# MCU.net
KiCad netlist of a schematic drawn in Altium Designer
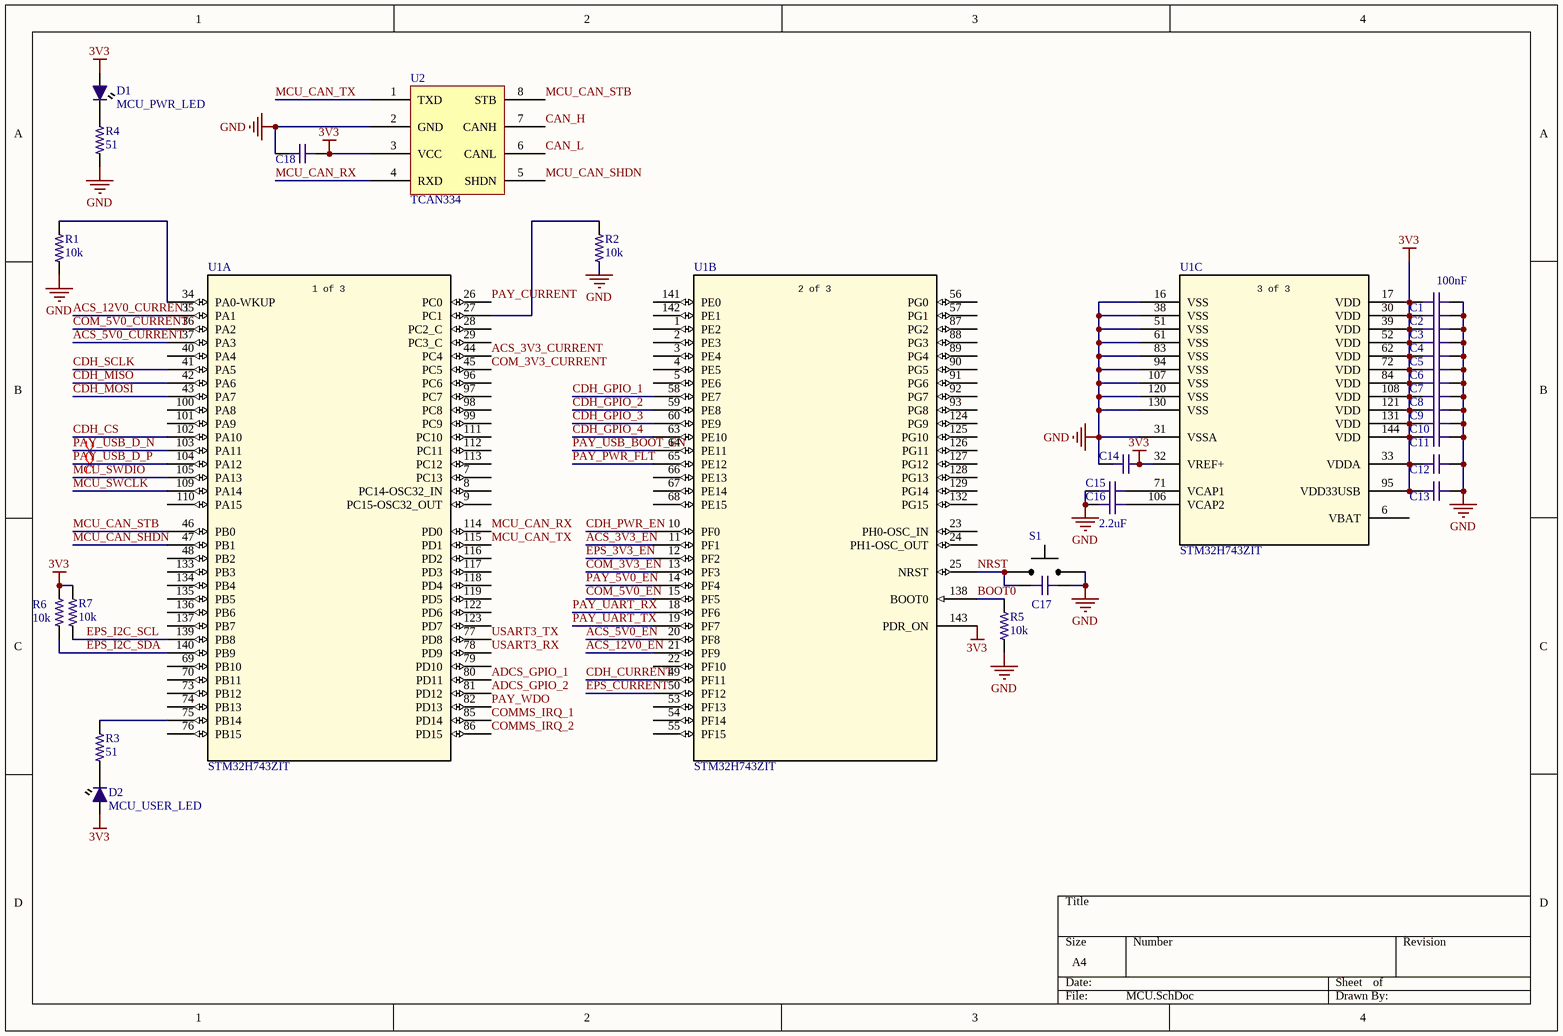
[diagram p0: MCU.SchDoc]

(export (version "E")
  (design (tool "Eeschema 10.0.6"))
  (components
    (comp (ref "C1")
      (value "100nF")
      (footprint "C0603-IPC")
      (description "Chip Capacitor, 0603, 100nF, 10V, X7R")
      (fields (field (name "Comment") "Capacitor"))
      (libsource (lib "UBC_Orbit_Shared_Components") (part "Capacitor"))
    )
    (comp (ref "C2")
      (value "Capacitor")
      (footprint "C0603-IPC")
      (description "Chip Capacitor, 0603, 100nF, 10V, X7R")
      (libsource (lib "UBC_Orbit_Shared_Components") (part "Capacitor"))
    )
    (comp (ref "C3")
      (value "Capacitor")
      (footprint "C0603-IPC")
      (description "Chip Capacitor, 0603, 100nF, 10V, X7R")
      (libsource (lib "UBC_Orbit_Shared_Components") (part "Capacitor"))
    )
    (comp (ref "C4")
      (value "Capacitor")
      (footprint "C0603-IPC")
      (description "Chip Capacitor, 0603, 100nF, 10V, X7R")
      (libsource (lib "UBC_Orbit_Shared_Components") (part "Capacitor"))
    )
    (comp (ref "C5")
      (value "Capacitor")
      (footprint "C0603-IPC")
      (description "Chip Capacitor, 0603, 100nF, 10V, X7R")
      (libsource (lib "UBC_Orbit_Shared_Components") (part "Capacitor"))
    )
    (comp (ref "C6")
      (value "Capacitor")
      (footprint "C0603-IPC")
      (description "Chip Capacitor, 0603, 100nF, 10V, X7R")
      (libsource (lib "UBC_Orbit_Shared_Components") (part "Capacitor"))
    )
    (comp (ref "C7")
      (value "Capacitor")
      (footprint "C0603-IPC")
      (description "Chip Capacitor, 0603, 100nF, 10V, X7R")
      (libsource (lib "UBC_Orbit_Shared_Components") (part "Capacitor"))
    )
    (comp (ref "C8")
      (value "Capacitor")
      (footprint "C0603-IPC")
      (description "Chip Capacitor, 0603, 100nF, 10V, X7R")
      (libsource (lib "UBC_Orbit_Shared_Components") (part "Capacitor"))
    )
    (comp (ref "C9")
      (value "Capacitor")
      (footprint "C0603-IPC")
      (description "Chip Capacitor, 0603, 100nF, 10V, X7R")
      (libsource (lib "UBC_Orbit_Shared_Components") (part "Capacitor"))
    )
    (comp (ref "C10")
      (value "Capacitor")
      (footprint "C0603-IPC")
      (description "Chip Capacitor, 0603, 100nF, 10V, X7R")
      (libsource (lib "UBC_Orbit_Shared_Components") (part "Capacitor"))
    )
    (comp (ref "C11")
      (value "Capacitor")
      (footprint "C0603-IPC")
      (description "Chip Capacitor, 0603, 100nF, 10V, X7R")
      (libsource (lib "UBC_Orbit_Shared_Components") (part "Capacitor"))
    )
    (comp (ref "C12")
      (value "Capacitor")
      (footprint "C0603-IPC")
      (description "Chip Capacitor, 0603, 100nF, 10V, X7R")
      (libsource (lib "UBC_Orbit_Shared_Components") (part "Capacitor"))
    )
    (comp (ref "C13")
      (value "Capacitor")
      (footprint "C0603-IPC")
      (description "Chip Capacitor, 0603, 100nF, 10V, X7R")
      (libsource (lib "UBC_Orbit_Shared_Components") (part "Capacitor"))
    )
    (comp (ref "C14")
      (value "Capacitor")
      (footprint "C0603-IPC")
      (description "Chip Capacitor, 0603, 10nF, 10V, X7R")
      (libsource (lib "UBC_Orbit_Shared_Components") (part "Capacitor"))
    )
    (comp (ref "C15")
      (value "Capacitor")
      (footprint "C0603-IPC")
      (description "Chip Capacitor, 0603, 2.2uF, 10V, X7R")
      (libsource (lib "UBC_Orbit_Shared_Components") (part "Capacitor"))
    )
    (comp (ref "C16")
      (value "2.2uF")
      (footprint "C0603-IPC")
      (description "Chip Capacitor, 0603, 2.2uF, 10V, X7R")
      (fields (field (name "Comment") "Capacitor"))
      (libsource (lib "UBC_Orbit_Shared_Components") (part "Capacitor"))
    )
    (comp (ref "C17")
      (value "Capacitor")
      (footprint "C0603-IPC")
      (description "Chip Capacitor, 0603, 100nF, 10V, X7R")
      (libsource (lib "UBC_Orbit_Shared_Components") (part "Capacitor"))
    )
    (comp (ref "C18")
      (value "Capacitor")
      (footprint "C0603-IPC")
      (description "Chip Capacitor, 0603, 100nF, 10V, X7R")
      (libsource (lib "UBC_Orbit_Shared_Components") (part "Capacitor"))
    )
    (comp (ref "D1")
      (value "MCU_PWR_LED")
      (footprint "LED0603-IPC")
      (description "Red PWR_LED")
      (libsource (lib "Diodes") (part "LED 0603 SMD"))
    )
    (comp (ref "D2")
      (value "MCU_USER_LED")
      (footprint "LED0603-IPC")
      (description "Blue DEBUG_LED")
      (libsource (lib "Diodes") (part "LED 0603 SMD"))
    )
    (comp (ref "R1")
      (value "10k")
      (footprint "R0603-IPC")
      (description "Resistor (0603)")
      (fields (field (name "Comment") "Resistor"))
      (libsource (lib "UBC_Orbit_Shared_Components") (part "Resistor"))
    )
    (comp (ref "R2")
      (value "10k")
      (footprint "R0603-IPC")
      (description "Resistor (0603)")
      (fields (field (name "Comment") "Resistor"))
      (libsource (lib "UBC_Orbit_Shared_Components") (part "Resistor"))
    )
    (comp (ref "R3")
      (value "51")
      (footprint "R0603-IPC")
      (description "Resistor (0603)")
      (fields (field (name "Comment") "Resistor"))
      (libsource (lib "UBC_Orbit_Shared_Components") (part "Resistor"))
    )
    (comp (ref "R4")
      (value "51")
      (footprint "R0603-IPC")
      (description "Chip Resistor, 0603, 51hms, 0.1W")
      (fields (field (name "Comment") "0603 Template"))
      (libsource (lib "Resistors") (part "0603 Template"))
    )
    (comp (ref "R5")
      (value "10k")
      (footprint "R0603-IPC")
      (description "Resistor (0603)")
      (fields (field (name "Comment") "Resistor"))
      (libsource (lib "UBC_Orbit_Shared_Components") (part "Resistor"))
    )
    (comp (ref "R6")
      (value "10k")
      (footprint "R0603-IPC")
      (description "Resistor (0603)")
      (fields (field (name "Comment") "Resistor"))
      (libsource (lib "UBC_Orbit_Shared_Components") (part "Resistor"))
    )
    (comp (ref "R7")
      (value "10k")
      (footprint "R0603-IPC")
      (description "Resistor (0603)")
      (fields (field (name "Comment") "Resistor"))
      (libsource (lib "UBC_Orbit_Shared_Components") (part "Resistor"))
    )
    (comp (ref "S1")
      (value "PTS810")
      (footprint "PTS810")
      (description "PTS810 Switch (Tactile)")
      (fields (field (name "MANUFACTURER") "C&K") (field (name "PART NUMBER") "PTS810 SJM 250 SMTR LFS"))
      (libsource (lib "UBC_Orbit_Shared_Components") (part "PTS810"))
    )
    (comp (ref "U1")
      (value "STM32H743ZIT")
      (footprint "LQFP50P2200X2200X160-144N")
      (description "STM32H743ZIT MCU")
      (fields (field (name "MANUFACTURER") "STMicroelectronics") (field (name "PART NUMBER") "STM32H743ZIT6"))
      (libsource (lib "UBC_Orbit_Shared_Components") (part "STM32H743ZIT"))
    )
    (comp (ref "U2")
      (value "TCAN334")
      (footprint "SOIC127P600X175-8N")
      (description "TCAN334 CAN Transceiver")
      (fields (field (name "MANUFACTURER") "Texas Instruments") (field (name "PART NUMBER") "TCAN334DCNT"))
      (libsource (lib "UBC_Orbit_Shared_Components") (part "TCAN334"))
    )
  )
  (nets
    (net (code "1") (name "/ACS_3V3_CURRENT") (class "Default")
      (node (ref "U1") (pin "44") (pinfunction "PC4_44") (pintype "bidirectional"))
    )
    (net (code "2") (name "/ACS_3V3_EN") (class "Default")
      (node (ref "U1") (pin "11") (pinfunction "PF1_11") (pintype "bidirectional"))
    )
    (net (code "3") (name "/ACS_5V0_CURRENT") (class "Default")
      (node (ref "U1") (pin "37") (pinfunction "PA3_37") (pintype "bidirectional"))
    )
    (net (code "4") (name "/ACS_5V0_EN") (class "Default")
      (node (ref "U1") (pin "20") (pinfunction "PF8_20") (pintype "bidirectional"))
    )
    (net (code "5") (name "/ACS_12V0_CURRENT") (class "Default")
      (node (ref "U1") (pin "35") (pinfunction "PA1_35") (pintype "bidirectional"))
    )
    (net (code "6") (name "/ACS_12V0_EN") (class "Default")
      (node (ref "U1") (pin "21") (pinfunction "PF9_21") (pintype "bidirectional"))
    )
    (net (code "7") (name "/ADCS_GPIO_1") (class "Default")
      (node (ref "U1") (pin "80") (pinfunction "PD11_80") (pintype "bidirectional"))
    )
    (net (code "8") (name "/ADCS_GPIO_2") (class "Default")
      (node (ref "U1") (pin "81") (pinfunction "PD12_81") (pintype "bidirectional"))
    )
    (net (code "9") (name "/BOOT0") (class "Default")
      (node (ref "R5") (pin "2") (pintype "passive"))
      (node (ref "U1") (pin "138") (pinfunction "BOOT0_138") (pintype "input"))
    )
    (net (code "10") (name "/CAN_H") (class "Default")
      (node (ref "U2") (pin "7") (pinfunction "CANH_7") (pintype "passive"))
    )
    (net (code "11") (name "/CAN_L") (class "Default")
      (node (ref "U2") (pin "6") (pinfunction "CANL_6") (pintype "passive"))
    )
    (net (code "12") (name "/CDH_CS") (class "Default")
      (node (ref "U1") (pin "102") (pinfunction "PA10_102") (pintype "bidirectional"))
    )
    (net (code "13") (name "/CDH_CURRENT") (class "Default")
      (node (ref "U1") (pin "49") (pinfunction "PF11_49") (pintype "bidirectional"))
    )
    (net (code "14") (name "/CDH_GPIO_1") (class "Default")
      (node (ref "U1") (pin "58") (pinfunction "PE7_58") (pintype "bidirectional"))
    )
    (net (code "15") (name "/CDH_GPIO_2") (class "Default")
      (node (ref "U1") (pin "59") (pinfunction "PE8_59") (pintype "bidirectional"))
    )
    (net (code "16") (name "/CDH_GPIO_3") (class "Default")
      (node (ref "U1") (pin "60") (pinfunction "PE9_60") (pintype "bidirectional"))
    )
    (net (code "17") (name "/CDH_GPIO_4") (class "Default")
      (node (ref "U1") (pin "63") (pinfunction "PE10_63") (pintype "bidirectional"))
    )
    (net (code "18") (name "/CDH_MISO") (class "Default")
      (node (ref "U1") (pin "42") (pinfunction "PA6_42") (pintype "bidirectional"))
    )
    (net (code "19") (name "/CDH_MOSI") (class "Default")
      (node (ref "U1") (pin "43") (pinfunction "PA7_43") (pintype "bidirectional"))
    )
    (net (code "20") (name "/CDH_PWR_EN") (class "Default")
      (node (ref "U1") (pin "10") (pinfunction "PF0_10") (pintype "bidirectional"))
    )
    (net (code "21") (name "/CDH_SCLK") (class "Default")
      (node (ref "U1") (pin "41") (pinfunction "PA5_41") (pintype "bidirectional"))
    )
    (net (code "22") (name "/COMMS_IRQ_1") (class "Default")
      (node (ref "U1") (pin "85") (pinfunction "PD14_85") (pintype "bidirectional"))
    )
    (net (code "23") (name "/COMMS_IRQ_2") (class "Default")
      (node (ref "U1") (pin "86") (pinfunction "PD15_86") (pintype "bidirectional"))
    )
    (net (code "24") (name "/COM_3V3_CURRENT") (class "Default")
      (node (ref "U1") (pin "45") (pinfunction "PC5_45") (pintype "bidirectional"))
    )
    (net (code "25") (name "/COM_3V3_EN") (class "Default")
      (node (ref "U1") (pin "13") (pinfunction "PF3_13") (pintype "bidirectional"))
    )
    (net (code "26") (name "/COM_5V0_CURRENT") (class "Default")
      (node (ref "U1") (pin "36") (pinfunction "PA2_36") (pintype "bidirectional"))
    )
    (net (code "27") (name "/COM_5V0_EN") (class "Default")
      (node (ref "U1") (pin "15") (pinfunction "PF5_15") (pintype "bidirectional"))
    )
    (net (code "28") (name "/EPS_3V3_EN") (class "Default")
      (node (ref "U1") (pin "12") (pinfunction "PF2_12") (pintype "bidirectional"))
    )
    (net (code "29") (name "/EPS_CURRENT") (class "Default")
      (node (ref "U1") (pin "50") (pinfunction "PF12_50") (pintype "bidirectional"))
    )
    (net (code "30") (name "/EPS_I2C_SCL") (class "Default")
      (node (ref "R7") (pin "1") (pintype "passive"))
      (node (ref "U1") (pin "139") (pinfunction "PB8_139") (pintype "bidirectional"))
    )
    (net (code "31") (name "/EPS_I2C_SDA") (class "Default")
      (node (ref "R6") (pin "1") (pintype "passive"))
      (node (ref "U1") (pin "140") (pinfunction "PB9_140") (pintype "bidirectional"))
    )
    (net (code "32") (name "/MCU_CAN_RX") (class "Default")
      (node (ref "U1") (pin "114") (pinfunction "PD0_114") (pintype "bidirectional"))
      (node (ref "U2") (pin "4") (pinfunction "RXD_4") (pintype "passive"))
    )
    (net (code "33") (name "/MCU_CAN_SHDN") (class "Default")
      (node (ref "U1") (pin "47") (pinfunction "PB1_47") (pintype "bidirectional"))
      (node (ref "U2") (pin "5") (pinfunction "SHDN_5") (pintype "passive"))
    )
    (net (code "34") (name "/MCU_CAN_STB") (class "Default")
      (node (ref "U1") (pin "46") (pinfunction "PB0_46") (pintype "bidirectional"))
      (node (ref "U2") (pin "8") (pinfunction "STB_8") (pintype "passive"))
    )
    (net (code "35") (name "/MCU_CAN_TX") (class "Default")
      (node (ref "U1") (pin "115") (pinfunction "PD1_115") (pintype "bidirectional"))
      (node (ref "U2") (pin "1") (pinfunction "TXD_1") (pintype "passive"))
    )
    (net (code "36") (name "/MCU_SWCLK") (class "Default")
      (node (ref "U1") (pin "109") (pinfunction "PA14_109") (pintype "bidirectional"))
    )
    (net (code "37") (name "/MCU_SWDIO") (class "Default")
      (node (ref "U1") (pin "105") (pinfunction "PA13_105") (pintype "bidirectional"))
    )
    (net (code "38") (name "/NRST") (class "Default")
      (node (ref "C17") (pin "1") (pintype "passive"))
      (node (ref "S1") (pin "1") (pinfunction "1_1") (pintype "passive"))
      (node (ref "U1") (pin "25") (pinfunction "NRST_25") (pintype "bidirectional"))
    )
    (net (code "39") (name "/PAY_5V0_EN") (class "Default")
      (node (ref "U1") (pin "14") (pinfunction "PF4_14") (pintype "bidirectional"))
    )
    (net (code "40") (name "/PAY_CURRENT") (class "Default")
      (node (ref "U1") (pin "26") (pinfunction "PC0_26") (pintype "bidirectional"))
    )
    (net (code "41") (name "/PAY_PWR_FLT") (class "Default")
      (node (ref "U1") (pin "65") (pinfunction "PE12_65") (pintype "bidirectional"))
    )
    (net (code "42") (name "/PAY_UART_RX") (class "Default")
      (node (ref "U1") (pin "18") (pinfunction "PF6_18") (pintype "bidirectional"))
    )
    (net (code "43") (name "/PAY_UART_TX") (class "Default")
      (node (ref "U1") (pin "19") (pinfunction "PF7_19") (pintype "bidirectional"))
    )
    (net (code "44") (name "/PAY_USB_BOOT_EN") (class "Default")
      (node (ref "U1") (pin "64") (pinfunction "PE11_64") (pintype "bidirectional"))
    )
    (net (code "45") (name "/PAY_USB_D_N") (class "Default")
      (node (ref "U1") (pin "103") (pinfunction "PA11_103") (pintype "bidirectional"))
    )
    (net (code "46") (name "/PAY_USB_D_P") (class "Default")
      (node (ref "U1") (pin "104") (pinfunction "PA12_104") (pintype "bidirectional"))
    )
    (net (code "47") (name "/PAY_WDO") (class "Default")
      (node (ref "U1") (pin "82") (pinfunction "PD13_82") (pintype "bidirectional"))
    )
    (net (code "48") (name "/USART3_RX") (class "Default")
      (node (ref "U1") (pin "78") (pinfunction "PD9_78") (pintype "bidirectional"))
    )
    (net (code "49") (name "/USART3_TX") (class "Default")
      (node (ref "U1") (pin "77") (pinfunction "PD8_77") (pintype "bidirectional"))
    )
    (net (code "50") (name "3V3") (class "Default")
      (node (ref "C1") (pin "1") (pintype "passive"))
      (node (ref "C10") (pin "1") (pintype "passive"))
      (node (ref "C11") (pin "1") (pintype "passive"))
      (node (ref "C12") (pin "1") (pintype "passive"))
      (node (ref "C13") (pin "1") (pintype "passive"))
      (node (ref "C14") (pin "2") (pintype "passive"))
      (node (ref "C18") (pin "2") (pintype "passive"))
      (node (ref "C2") (pin "1") (pintype "passive"))
      (node (ref "C3") (pin "1") (pintype "passive"))
      (node (ref "C4") (pin "1") (pintype "passive"))
      (node (ref "C5") (pin "1") (pintype "passive"))
      (node (ref "C6") (pin "1") (pintype "passive"))
      (node (ref "C7") (pin "1") (pintype "passive"))
      (node (ref "C8") (pin "1") (pintype "passive"))
      (node (ref "C9") (pin "1") (pintype "passive"))
      (node (ref "D1") (pin "A") (pintype "passive"))
      (node (ref "D2") (pin "A") (pintype "passive"))
      (node (ref "R6") (pin "2") (pintype "passive"))
      (node (ref "R7") (pin "2") (pintype "passive"))
      (node (ref "U1") (pin "108") (pinfunction "VDD_108") (pintype "power_in"))
      (node (ref "U1") (pin "121") (pinfunction "VDD_121") (pintype "power_in"))
      (node (ref "U1") (pin "131") (pinfunction "VDD_131") (pintype "power_in"))
      (node (ref "U1") (pin "143") (pinfunction "PDR_ON_143") (pintype "passive"))
      (node (ref "U1") (pin "144") (pinfunction "VDD_144") (pintype "power_in"))
      (node (ref "U1") (pin "17") (pinfunction "VDD_17") (pintype "power_in"))
      (node (ref "U1") (pin "30") (pinfunction "VDD_30") (pintype "power_in"))
      (node (ref "U1") (pin "32") (pinfunction "VREF+_32") (pintype "power_in"))
      (node (ref "U1") (pin "33") (pinfunction "VDDA_33") (pintype "power_in"))
      (node (ref "U1") (pin "39") (pinfunction "VDD_39") (pintype "power_in"))
      (node (ref "U1") (pin "52") (pinfunction "VDD_52") (pintype "power_in"))
      (node (ref "U1") (pin "62") (pinfunction "VDD_62") (pintype "power_in"))
      (node (ref "U1") (pin "72") (pinfunction "VDD_72") (pintype "power_in"))
      (node (ref "U1") (pin "84") (pinfunction "VDD_84") (pintype "power_in"))
      (node (ref "U1") (pin "95") (pinfunction "VDD33USB_95") (pintype "power_in"))
      (node (ref "U2") (pin "3") (pinfunction "VCC_3") (pintype "passive"))
    )
    (net (code "51") (name "GND") (class "Default")
      (node (ref "C1") (pin "2") (pintype "passive"))
      (node (ref "C10") (pin "2") (pintype "passive"))
      (node (ref "C11") (pin "2") (pintype "passive"))
      (node (ref "C12") (pin "2") (pintype "passive"))
      (node (ref "C13") (pin "2") (pintype "passive"))
      (node (ref "C14") (pin "1") (pintype "passive"))
      (node (ref "C15") (pin "1") (pintype "passive"))
      (node (ref "C16") (pin "1") (pintype "passive"))
      (node (ref "C17") (pin "2") (pintype "passive"))
      (node (ref "C18") (pin "1") (pintype "passive"))
      (node (ref "C2") (pin "2") (pintype "passive"))
      (node (ref "C3") (pin "2") (pintype "passive"))
      (node (ref "C4") (pin "2") (pintype "passive"))
      (node (ref "C5") (pin "2") (pintype "passive"))
      (node (ref "C6") (pin "2") (pintype "passive"))
      (node (ref "C7") (pin "2") (pintype "passive"))
      (node (ref "C8") (pin "2") (pintype "passive"))
      (node (ref "C9") (pin "2") (pintype "passive"))
      (node (ref "R1") (pin "1") (pintype "passive"))
      (node (ref "R2") (pin "1") (pintype "passive"))
      (node (ref "R4") (pin "2") (pintype "passive"))
      (node (ref "R5") (pin "1") (pintype "passive"))
      (node (ref "S1") (pin "2") (pinfunction "2_2") (pintype "passive"))
      (node (ref "U1") (pin "107") (pinfunction "VSS_107") (pintype "power_in"))
      (node (ref "U1") (pin "120") (pinfunction "VSS_120") (pintype "power_in"))
      (node (ref "U1") (pin "130") (pinfunction "VSS_130") (pintype "power_in"))
      (node (ref "U1") (pin "16") (pinfunction "VSS_16") (pintype "power_in"))
      (node (ref "U1") (pin "31") (pinfunction "VSSA_31") (pintype "power_in"))
      (node (ref "U1") (pin "38") (pinfunction "VSS_38") (pintype "power_in"))
      (node (ref "U1") (pin "51") (pinfunction "VSS_51") (pintype "power_in"))
      (node (ref "U1") (pin "61") (pinfunction "VSS_61") (pintype "power_in"))
      (node (ref "U1") (pin "83") (pinfunction "VSS_83") (pintype "power_in"))
      (node (ref "U1") (pin "94") (pinfunction "VSS_94") (pintype "power_in"))
      (node (ref "U2") (pin "2") (pinfunction "GND_2") (pintype "passive"))
    )
    (net (code "52") (name "Net-(D1-PadK)") (class "Default")
      (node (ref "D1") (pin "K") (pintype "passive"))
      (node (ref "R4") (pin "1") (pintype "passive"))
    )
    (net (code "53") (name "Net-(D2-PadK)") (class "Default")
      (node (ref "D2") (pin "K") (pintype "passive"))
      (node (ref "R3") (pin "1") (pintype "passive"))
    )
    (net (code "54") (name "Net-(U1A-PA0-WKUP)") (class "Default")
      (node (ref "R1") (pin "2") (pintype "passive"))
      (node (ref "U1") (pin "34") (pinfunction "PA0-WKUP_34") (pintype "bidirectional"))
    )
    (net (code "55") (name "Net-(U1A-PB14)") (class "Default")
      (node (ref "R3") (pin "2") (pintype "passive"))
      (node (ref "U1") (pin "75") (pinfunction "PB14_75") (pintype "bidirectional"))
    )
    (net (code "56") (name "Net-(U1A-PC1)") (class "Default")
      (node (ref "R2") (pin "2") (pintype "passive"))
      (node (ref "U1") (pin "27") (pinfunction "PC1_27") (pintype "bidirectional"))
    )
    (net (code "57") (name "Net-(U1C-VCAP1)") (class "Default")
      (node (ref "C15") (pin "2") (pintype "passive"))
      (node (ref "U1") (pin "71") (pinfunction "VCAP1_71") (pintype "power_in"))
    )
    (net (code "58") (name "Net-(U1C-VCAP2)") (class "Default")
      (node (ref "C16") (pin "2") (pintype "passive"))
      (node (ref "U1") (pin "106") (pinfunction "VCAP2_106") (pintype "power_in"))
    )
    (net (code "59") (name "unconnected-(U1A-PA4-Pad40)") (class "Default")
      (node (ref "U1") (pin "40") (pinfunction "PA4_40") (pintype "bidirectional"))
    )
    (net (code "60") (name "unconnected-(U1A-PA8-Pad100)") (class "Default")
      (node (ref "U1") (pin "100") (pinfunction "PA8_100") (pintype "bidirectional"))
    )
    (net (code "61") (name "unconnected-(U1A-PA9-Pad101)") (class "Default")
      (node (ref "U1") (pin "101") (pinfunction "PA9_101") (pintype "bidirectional"))
    )
    (net (code "62") (name "unconnected-(U1A-PA15-Pad110)") (class "Default")
      (node (ref "U1") (pin "110") (pinfunction "PA15_110") (pintype "bidirectional"))
    )
    (net (code "63") (name "unconnected-(U1A-PB2-Pad48)") (class "Default")
      (node (ref "U1") (pin "48") (pinfunction "PB2_48") (pintype "bidirectional"))
    )
    (net (code "64") (name "unconnected-(U1A-PB3-Pad133)") (class "Default")
      (node (ref "U1") (pin "133") (pinfunction "PB3_133") (pintype "bidirectional"))
    )
    (net (code "65") (name "unconnected-(U1A-PB4-Pad134)") (class "Default")
      (node (ref "U1") (pin "134") (pinfunction "PB4_134") (pintype "bidirectional"))
    )
    (net (code "66") (name "unconnected-(U1A-PB5-Pad135)") (class "Default")
      (node (ref "U1") (pin "135") (pinfunction "PB5_135") (pintype "bidirectional"))
    )
    (net (code "67") (name "unconnected-(U1A-PB6-Pad136)") (class "Default")
      (node (ref "U1") (pin "136") (pinfunction "PB6_136") (pintype "bidirectional"))
    )
    (net (code "68") (name "unconnected-(U1A-PB7-Pad137)") (class "Default")
      (node (ref "U1") (pin "137") (pinfunction "PB7_137") (pintype "bidirectional"))
    )
    (net (code "69") (name "unconnected-(U1A-PB10-Pad69)") (class "Default")
      (node (ref "U1") (pin "69") (pinfunction "PB10_69") (pintype "bidirectional"))
    )
    (net (code "70") (name "unconnected-(U1A-PB11-Pad70)") (class "Default")
      (node (ref "U1") (pin "70") (pinfunction "PB11_70") (pintype "bidirectional"))
    )
    (net (code "71") (name "unconnected-(U1A-PB12-Pad73)") (class "Default")
      (node (ref "U1") (pin "73") (pinfunction "PB12_73") (pintype "bidirectional"))
    )
    (net (code "72") (name "unconnected-(U1A-PB13-Pad74)") (class "Default")
      (node (ref "U1") (pin "74") (pinfunction "PB13_74") (pintype "bidirectional"))
    )
    (net (code "73") (name "unconnected-(U1A-PB15-Pad76)") (class "Default")
      (node (ref "U1") (pin "76") (pinfunction "PB15_76") (pintype "bidirectional"))
    )
    (net (code "74") (name "unconnected-(U1A-PC2_C-Pad28)") (class "Default")
      (node (ref "U1") (pin "28") (pinfunction "PC2_C_28") (pintype "bidirectional"))
    )
    (net (code "75") (name "unconnected-(U1A-PC3_C-Pad29)") (class "Default")
      (node (ref "U1") (pin "29") (pinfunction "PC3_C_29") (pintype "bidirectional"))
    )
    (net (code "76") (name "unconnected-(U1A-PC6-Pad96)") (class "Default")
      (node (ref "U1") (pin "96") (pinfunction "PC6_96") (pintype "bidirectional"))
    )
    (net (code "77") (name "unconnected-(U1A-PC7-Pad97)") (class "Default")
      (node (ref "U1") (pin "97") (pinfunction "PC7_97") (pintype "bidirectional"))
    )
    (net (code "78") (name "unconnected-(U1A-PC8-Pad98)") (class "Default")
      (node (ref "U1") (pin "98") (pinfunction "PC8_98") (pintype "bidirectional"))
    )
    (net (code "79") (name "unconnected-(U1A-PC9-Pad99)") (class "Default")
      (node (ref "U1") (pin "99") (pinfunction "PC9_99") (pintype "bidirectional"))
    )
    (net (code "80") (name "unconnected-(U1A-PC10-Pad111)") (class "Default")
      (node (ref "U1") (pin "111") (pinfunction "PC10_111") (pintype "bidirectional"))
    )
    (net (code "81") (name "unconnected-(U1A-PC11-Pad112)") (class "Default")
      (node (ref "U1") (pin "112") (pinfunction "PC11_112") (pintype "bidirectional"))
    )
    (net (code "82") (name "unconnected-(U1A-PC12-Pad113)") (class "Default")
      (node (ref "U1") (pin "113") (pinfunction "PC12_113") (pintype "bidirectional"))
    )
    (net (code "83") (name "unconnected-(U1A-PC13-Pad7)") (class "Default")
      (node (ref "U1") (pin "7") (pinfunction "PC13_7") (pintype "bidirectional"))
    )
    (net (code "84") (name "unconnected-(U1A-PC14-OSC32_IN-Pad8)") (class "Default")
      (node (ref "U1") (pin "8") (pinfunction "PC14-OSC32_IN_8") (pintype "bidirectional"))
    )
    (net (code "85") (name "unconnected-(U1A-PC15-OSC32_OUT-Pad9)") (class "Default")
      (node (ref "U1") (pin "9") (pinfunction "PC15-OSC32_OUT_9") (pintype "bidirectional"))
    )
    (net (code "86") (name "unconnected-(U1A-PD2-Pad116)") (class "Default")
      (node (ref "U1") (pin "116") (pinfunction "PD2_116") (pintype "bidirectional"))
    )
    (net (code "87") (name "unconnected-(U1A-PD3-Pad117)") (class "Default")
      (node (ref "U1") (pin "117") (pinfunction "PD3_117") (pintype "bidirectional"))
    )
    (net (code "88") (name "unconnected-(U1A-PD4-Pad118)") (class "Default")
      (node (ref "U1") (pin "118") (pinfunction "PD4_118") (pintype "bidirectional"))
    )
    (net (code "89") (name "unconnected-(U1A-PD5-Pad119)") (class "Default")
      (node (ref "U1") (pin "119") (pinfunction "PD5_119") (pintype "bidirectional"))
    )
    (net (code "90") (name "unconnected-(U1A-PD6-Pad122)") (class "Default")
      (node (ref "U1") (pin "122") (pinfunction "PD6_122") (pintype "bidirectional"))
    )
    (net (code "91") (name "unconnected-(U1A-PD7-Pad123)") (class "Default")
      (node (ref "U1") (pin "123") (pinfunction "PD7_123") (pintype "bidirectional"))
    )
    (net (code "92") (name "unconnected-(U1A-PD10-Pad79)") (class "Default")
      (node (ref "U1") (pin "79") (pinfunction "PD10_79") (pintype "bidirectional"))
    )
    (net (code "93") (name "unconnected-(U1B-PE0-Pad141)") (class "Default")
      (node (ref "U1") (pin "141") (pinfunction "PE0_141") (pintype "bidirectional"))
    )
    (net (code "94") (name "unconnected-(U1B-PE1-Pad142)") (class "Default")
      (node (ref "U1") (pin "142") (pinfunction "PE1_142") (pintype "bidirectional"))
    )
    (net (code "95") (name "unconnected-(U1B-PE2-Pad1)") (class "Default")
      (node (ref "U1") (pin "1") (pinfunction "PE2_1") (pintype "bidirectional"))
    )
    (net (code "96") (name "unconnected-(U1B-PE3-Pad2)") (class "Default")
      (node (ref "U1") (pin "2") (pinfunction "PE3_2") (pintype "bidirectional"))
    )
    (net (code "97") (name "unconnected-(U1B-PE4-Pad3)") (class "Default")
      (node (ref "U1") (pin "3") (pinfunction "PE4_3") (pintype "bidirectional"))
    )
    (net (code "98") (name "unconnected-(U1B-PE5-Pad4)") (class "Default")
      (node (ref "U1") (pin "4") (pinfunction "PE5_4") (pintype "bidirectional"))
    )
    (net (code "99") (name "unconnected-(U1B-PE6-Pad5)") (class "Default")
      (node (ref "U1") (pin "5") (pinfunction "PE6_5") (pintype "bidirectional"))
    )
    (net (code "100") (name "unconnected-(U1B-PE13-Pad66)") (class "Default")
      (node (ref "U1") (pin "66") (pinfunction "PE13_66") (pintype "bidirectional"))
    )
    (net (code "101") (name "unconnected-(U1B-PE14-Pad67)") (class "Default")
      (node (ref "U1") (pin "67") (pinfunction "PE14_67") (pintype "bidirectional"))
    )
    (net (code "102") (name "unconnected-(U1B-PE15-Pad68)") (class "Default")
      (node (ref "U1") (pin "68") (pinfunction "PE15_68") (pintype "bidirectional"))
    )
    (net (code "103") (name "unconnected-(U1B-PF10-Pad22)") (class "Default")
      (node (ref "U1") (pin "22") (pinfunction "PF10_22") (pintype "bidirectional"))
    )
    (net (code "104") (name "unconnected-(U1B-PF13-Pad53)") (class "Default")
      (node (ref "U1") (pin "53") (pinfunction "PF13_53") (pintype "bidirectional"))
    )
    (net (code "105") (name "unconnected-(U1B-PF14-Pad54)") (class "Default")
      (node (ref "U1") (pin "54") (pinfunction "PF14_54") (pintype "bidirectional"))
    )
    (net (code "106") (name "unconnected-(U1B-PF15-Pad55)") (class "Default")
      (node (ref "U1") (pin "55") (pinfunction "PF15_55") (pintype "bidirectional"))
    )
    (net (code "107") (name "unconnected-(U1B-PG0-Pad56)") (class "Default")
      (node (ref "U1") (pin "56") (pinfunction "PG0_56") (pintype "bidirectional"))
    )
    (net (code "108") (name "unconnected-(U1B-PG1-Pad57)") (class "Default")
      (node (ref "U1") (pin "57") (pinfunction "PG1_57") (pintype "bidirectional"))
    )
    (net (code "109") (name "unconnected-(U1B-PG2-Pad87)") (class "Default")
      (node (ref "U1") (pin "87") (pinfunction "PG2_87") (pintype "bidirectional"))
    )
    (net (code "110") (name "unconnected-(U1B-PG3-Pad88)") (class "Default")
      (node (ref "U1") (pin "88") (pinfunction "PG3_88") (pintype "bidirectional"))
    )
    (net (code "111") (name "unconnected-(U1B-PG4-Pad89)") (class "Default")
      (node (ref "U1") (pin "89") (pinfunction "PG4_89") (pintype "bidirectional"))
    )
    (net (code "112") (name "unconnected-(U1B-PG5-Pad90)") (class "Default")
      (node (ref "U1") (pin "90") (pinfunction "PG5_90") (pintype "bidirectional"))
    )
    (net (code "113") (name "unconnected-(U1B-PG6-Pad91)") (class "Default")
      (node (ref "U1") (pin "91") (pinfunction "PG6_91") (pintype "bidirectional"))
    )
    (net (code "114") (name "unconnected-(U1B-PG7-Pad92)") (class "Default")
      (node (ref "U1") (pin "92") (pinfunction "PG7_92") (pintype "bidirectional"))
    )
    (net (code "115") (name "unconnected-(U1B-PG8-Pad93)") (class "Default")
      (node (ref "U1") (pin "93") (pinfunction "PG8_93") (pintype "bidirectional"))
    )
    (net (code "116") (name "unconnected-(U1B-PG9-Pad124)") (class "Default")
      (node (ref "U1") (pin "124") (pinfunction "PG9_124") (pintype "bidirectional"))
    )
    (net (code "117") (name "unconnected-(U1B-PG10-Pad125)") (class "Default")
      (node (ref "U1") (pin "125") (pinfunction "PG10_125") (pintype "bidirectional"))
    )
    (net (code "118") (name "unconnected-(U1B-PG11-Pad126)") (class "Default")
      (node (ref "U1") (pin "126") (pinfunction "PG11_126") (pintype "bidirectional"))
    )
    (net (code "119") (name "unconnected-(U1B-PG12-Pad127)") (class "Default")
      (node (ref "U1") (pin "127") (pinfunction "PG12_127") (pintype "bidirectional"))
    )
    (net (code "120") (name "unconnected-(U1B-PG13-Pad128)") (class "Default")
      (node (ref "U1") (pin "128") (pinfunction "PG13_128") (pintype "bidirectional"))
    )
    (net (code "121") (name "unconnected-(U1B-PG14-Pad129)") (class "Default")
      (node (ref "U1") (pin "129") (pinfunction "PG14_129") (pintype "bidirectional"))
    )
    (net (code "122") (name "unconnected-(U1B-PG15-Pad132)") (class "Default")
      (node (ref "U1") (pin "132") (pinfunction "PG15_132") (pintype "bidirectional"))
    )
    (net (code "123") (name "unconnected-(U1B-PH0-OSC_IN-Pad23)") (class "Default")
      (node (ref "U1") (pin "23") (pinfunction "PH0-OSC_IN_23") (pintype "bidirectional"))
    )
    (net (code "124") (name "unconnected-(U1B-PH1-OSC_OUT-Pad24)") (class "Default")
      (node (ref "U1") (pin "24") (pinfunction "PH1-OSC_OUT_24") (pintype "bidirectional"))
    )
    (net (code "125") (name "unconnected-(U1C-VBAT-Pad6)") (class "Default")
      (node (ref "U1") (pin "6") (pinfunction "VBAT_6") (pintype "power_in"))
    )
  )
)
